# board1.net
KiCad netlist of a schematic drawn in EAGLE
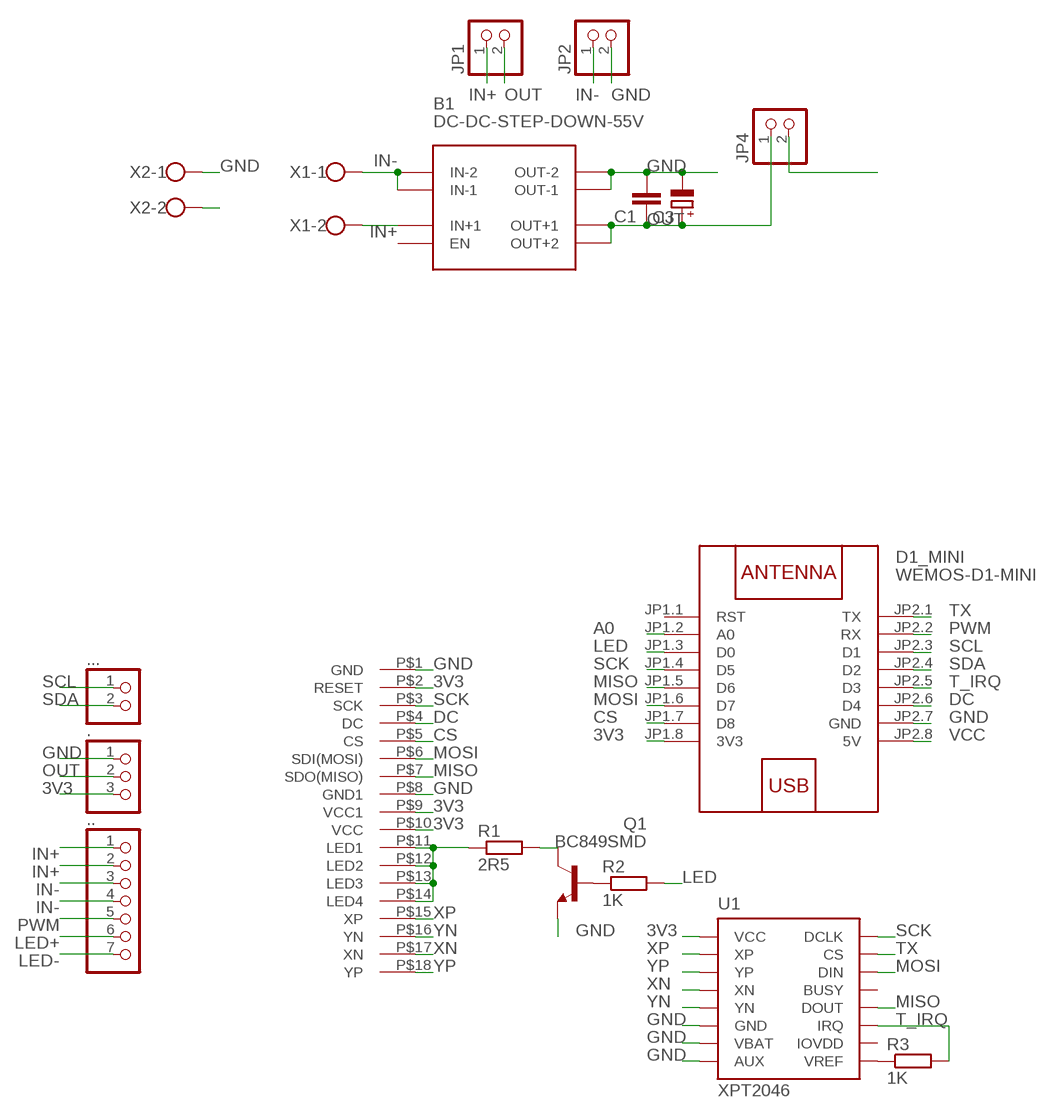
[diagram p0: schematic, sheet 1]

(export (version "E")
  (design (tool "Eeschema 10.0.6"))
  (components
    (comp (ref ".")
      (value "PINHD-1X3")
      (footprint "eagle-import:1X03")
      (libsource (lib "eagle-import") (part "PINHD-1X3"))
    )
    (comp (ref "..")
      (value "PINHD-1X7")
      (footprint "eagle-import:1X07")
      (libsource (lib "eagle-import") (part "PINHD-1X7"))
    )
    (comp (ref "...")
      (value "PINHD-1X2")
      (footprint "eagle-import:1X02")
      (libsource (lib "eagle-import") (part "PINHD-1X2"))
    )
    (comp (ref "B1")
      (value "DC-DC-STEP-DOWN-55V")
      (footprint "eagle-import:DC-DC-STEP-DOWN-55V")
      (libsource (lib "eagle-import") (part "DC-DC-STEP-DOWN-55V"))
    )
    (comp (ref "C1")
      (value "C-EUC0805")
      (footprint "eagle-import:C0805")
      (libsource (lib "eagle-import") (part "C-EUC0805"))
    )
    (comp (ref "C3")
      (value "CPOL-EUE2-5")
      (footprint "eagle-import:E2-5")
      (libsource (lib "eagle-import") (part "CPOL-EUE2-5"))
    )
    (comp (ref "D1_MINI")
      (value "WEMOS-D1-MINI")
      (footprint "eagle-import:WEMOS-D1-MINI")
      (libsource (lib "eagle-import") (part "WEMOS-D1-MINI"))
    )
    (comp (ref "JP1")
      (value "PINHD-1X2")
      (footprint "eagle-import:1X02")
      (libsource (lib "eagle-import") (part "PINHD-1X2"))
    )
    (comp (ref "JP2")
      (value "PINHD-1X2")
      (footprint "eagle-import:1X02")
      (libsource (lib "eagle-import") (part "PINHD-1X2"))
    )
    (comp (ref "JP4")
      (value "PINHD-1X2")
      (footprint "eagle-import:1X02")
      (libsource (lib "eagle-import") (part "PINHD-1X2"))
    )
    (comp (ref "Q1")
      (value "BC849SMD")
      (footprint "eagle-import:SOT23-BEC")
      (libsource (lib "eagle-import") (part "BC849SMD"))
    )
    (comp (ref "R1")
      (value "2R5")
      (footprint "eagle-import:R1210W")
      (libsource (lib "eagle-import") (part "R-EU_R1210W"))
    )
    (comp (ref "R2")
      (value "1K")
      (footprint "eagle-import:R1210W")
      (libsource (lib "eagle-import") (part "R-EU_R1210W"))
    )
    (comp (ref "R3")
      (value "1K")
      (footprint "eagle-import:R1210W")
      (libsource (lib "eagle-import") (part "R-EU_R1210W"))
    )
    (comp (ref "U$2")
      (value "2.4TTF")
      (footprint "eagle-import:TFT2.4")
      (libsource (lib "eagle-import") (part "2.4TTF"))
    )
    (comp (ref "U1")
      (value "XPT2046")
      (footprint "eagle-import:TSSOP16")
      (libsource (lib "eagle-import") (part "XPT2046"))
    )
    (comp (ref "X1")
      (value "W237-102")
      (footprint "eagle-import:W237-102")
      (fields (field (name "MPN") "237-102"))
      (libsource (lib "eagle-import") (part "W237-102"))
    )
    (comp (ref "X2")
      (value "W237-102")
      (footprint "eagle-import:W237-102")
      (fields (field (name "MPN") "237-102"))
      (libsource (lib "eagle-import") (part "W237-102"))
    )
  )
  (nets
    (net (code "1") (name "/3V3") (class "Default")
      (node (ref ".") (pin "3") (pinfunction "3_3") (pintype "passive"))
      (node (ref "D1_MINI") (pin "JP1.8") (pinfunction "3V3_JP1.8") (pintype "power_in"))
      (node (ref "U$2") (pin "P$10") (pinfunction "VCC_P$10") (pintype "bidirectional"))
      (node (ref "U$2") (pin "P$2") (pinfunction "RESET_P$2") (pintype "bidirectional"))
      (node (ref "U$2") (pin "P$9") (pinfunction "VCC1_P$9") (pintype "bidirectional"))
      (node (ref "U1") (pin "1") (pinfunction "VCC_1") (pintype "power_in"))
    )
    (net (code "2") (name "/A0") (class "Default")
      (node (ref "D1_MINI") (pin "JP1.2") (pinfunction "A0_JP1.2") (pintype "bidirectional"))
      (node (ref "X2") (pin "2") (pinfunction "KL_2") (pintype "passive"))
    )
    (net (code "3") (name "/CS") (class "Default")
      (node (ref "D1_MINI") (pin "JP1.7") (pinfunction "D8_JP1.7") (pintype "bidirectional"))
      (node (ref "U$2") (pin "P$5") (pinfunction "CS_P$5") (pintype "bidirectional"))
    )
    (net (code "4") (name "/DC") (class "Default")
      (node (ref "D1_MINI") (pin "JP2.6") (pinfunction "D4_JP2.6") (pintype "bidirectional"))
      (node (ref "U$2") (pin "P$4") (pinfunction "DC_P$4") (pintype "bidirectional"))
    )
    (net (code "5") (name "/GND") (class "Default")
      (node (ref ".") (pin "1") (pinfunction "1_1") (pintype "passive"))
      (node (ref "B1") (pin "VOUT-1") (pinfunction "OUT-1_VOUT-1") (pintype "bidirectional"))
      (node (ref "B1") (pin "VOUT-2") (pinfunction "OUT-2_VOUT-2") (pintype "bidirectional"))
      (node (ref "C1") (pin "2") (pinfunction "2_2") (pintype "passive"))
      (node (ref "C3") (pin "-") (pinfunction "-_-") (pintype "passive"))
      (node (ref "D1_MINI") (pin "JP2.7") (pinfunction "GND_JP2.7") (pintype "power_in"))
      (node (ref "JP2") (pin "2") (pinfunction "2_2") (pintype "passive"))
      (node (ref "Q1") (pin "E") (pinfunction "E_E") (pintype "passive"))
      (node (ref "U$2") (pin "P$1") (pinfunction "GND_P$1") (pintype "power_in"))
      (node (ref "U$2") (pin "P$8") (pinfunction "GND1_P$8") (pintype "power_in"))
      (node (ref "U1") (pin "6") (pinfunction "GND_6") (pintype "power_in"))
      (node (ref "U1") (pin "7") (pinfunction "VBAT_7") (pintype "bidirectional"))
      (node (ref "U1") (pin "8") (pinfunction "AUX_8") (pintype "bidirectional"))
      (node (ref "X2") (pin "1") (pinfunction "KL_1") (pintype "passive"))
    )
    (net (code "6") (name "/IN+") (class "Default")
      (node (ref "..") (pin "1") (pinfunction "1_1") (pintype "passive"))
      (node (ref "..") (pin "2") (pinfunction "2_2") (pintype "passive"))
      (node (ref "B1") (pin "VIN+") (pinfunction "IN+1_VIN+") (pintype "bidirectional"))
      (node (ref "JP1") (pin "1") (pinfunction "1_1") (pintype "passive"))
      (node (ref "X1") (pin "2") (pinfunction "KL_2") (pintype "passive"))
    )
    (net (code "7") (name "/IN-") (class "Default")
      (node (ref "..") (pin "3") (pinfunction "3_3") (pintype "passive"))
      (node (ref "..") (pin "4") (pinfunction "4_4") (pintype "passive"))
      (node (ref "B1") (pin "VIN-1") (pinfunction "IN-1_VIN-1") (pintype "bidirectional"))
      (node (ref "B1") (pin "VIN-2") (pinfunction "IN-2_VIN-2") (pintype "bidirectional"))
      (node (ref "JP2") (pin "1") (pinfunction "1_1") (pintype "passive"))
      (node (ref "X1") (pin "1") (pinfunction "KL_1") (pintype "passive"))
    )
    (net (code "8") (name "/LED") (class "Default")
      (node (ref "D1_MINI") (pin "JP1.3") (pinfunction "D0_JP1.3") (pintype "bidirectional"))
      (node (ref "R2") (pin "2") (pinfunction "2_2") (pintype "passive"))
    )
    (net (code "9") (name "/LED+") (class "Default")
      (node (ref "..") (pin "6") (pinfunction "6_6") (pintype "passive"))
    )
    (net (code "10") (name "/LED-") (class "Default")
      (node (ref "..") (pin "7") (pinfunction "7_7") (pintype "passive"))
    )
    (net (code "11") (name "/MISO") (class "Default")
      (node (ref "D1_MINI") (pin "JP1.5") (pinfunction "D6_JP1.5") (pintype "bidirectional"))
      (node (ref "U$2") (pin "P$7") (pinfunction "SDO(MISO)_P$7") (pintype "bidirectional"))
      (node (ref "U1") (pin "12") (pinfunction "DOUT_12") (pintype "output"))
    )
    (net (code "12") (name "/MOSI") (class "Default")
      (node (ref "D1_MINI") (pin "JP1.6") (pinfunction "D7_JP1.6") (pintype "bidirectional"))
      (node (ref "U$2") (pin "P$6") (pinfunction "SDI(MOSI)_P$6") (pintype "bidirectional"))
      (node (ref "U1") (pin "14") (pinfunction "DIN_14") (pintype "input"))
    )
    (net (code "13") (name "/OUT") (class "Default")
      (node (ref ".") (pin "2") (pinfunction "2_2") (pintype "passive"))
      (node (ref "B1") (pin "VOUT+1") (pinfunction "OUT+1_VOUT+1") (pintype "bidirectional"))
      (node (ref "B1") (pin "VOUT+2") (pinfunction "OUT+2_VOUT+2") (pintype "bidirectional"))
      (node (ref "C1") (pin "1") (pinfunction "1_1") (pintype "passive"))
      (node (ref "C3") (pin "+") (pinfunction "+_+") (pintype "passive"))
      (node (ref "JP1") (pin "2") (pinfunction "2_2") (pintype "passive"))
      (node (ref "JP4") (pin "1") (pinfunction "1_1") (pintype "passive"))
    )
    (net (code "14") (name "/PWM") (class "Default")
      (node (ref "..") (pin "5") (pinfunction "5_5") (pintype "passive"))
      (node (ref "D1_MINI") (pin "JP2.2") (pinfunction "RX_JP2.2") (pintype "bidirectional"))
    )
    (net (code "15") (name "/SCK") (class "Default")
      (node (ref "D1_MINI") (pin "JP1.4") (pinfunction "D5_JP1.4") (pintype "bidirectional"))
      (node (ref "U$2") (pin "P$3") (pinfunction "SCK_P$3") (pintype "bidirectional"))
      (node (ref "U1") (pin "16") (pinfunction "DCLK_16") (pintype "input"))
    )
    (net (code "16") (name "/SCL") (class "Default")
      (node (ref "...") (pin "1") (pinfunction "1_1") (pintype "passive"))
      (node (ref "D1_MINI") (pin "JP2.3") (pinfunction "D1_JP2.3") (pintype "bidirectional"))
    )
    (net (code "17") (name "/SDA") (class "Default")
      (node (ref "...") (pin "2") (pinfunction "2_2") (pintype "passive"))
      (node (ref "D1_MINI") (pin "JP2.4") (pinfunction "D2_JP2.4") (pintype "bidirectional"))
    )
    (net (code "18") (name "/TX") (class "Default")
      (node (ref "D1_MINI") (pin "JP2.1") (pinfunction "TX_JP2.1") (pintype "bidirectional"))
      (node (ref "U1") (pin "15") (pinfunction "CS_15") (pintype "bidirectional"))
    )
    (net (code "19") (name "/T_IRQ") (class "Default")
      (node (ref "D1_MINI") (pin "JP2.5") (pinfunction "D3_JP2.5") (pintype "bidirectional"))
      (node (ref "R3") (pin "2") (pinfunction "2_2") (pintype "passive"))
      (node (ref "U1") (pin "11") (pinfunction "IRQ_11") (pintype "bidirectional"))
    )
    (net (code "20") (name "/VCC") (class "Default")
      (node (ref "D1_MINI") (pin "JP2.8") (pinfunction "5V_JP2.8") (pintype "power_in"))
      (node (ref "JP4") (pin "2") (pinfunction "2_2") (pintype "passive"))
    )
    (net (code "21") (name "/XN") (class "Default")
      (node (ref "U$2") (pin "P$17") (pinfunction "XN_P$17") (pintype "bidirectional"))
      (node (ref "U1") (pin "4") (pinfunction "XN_4") (pintype "bidirectional"))
    )
    (net (code "22") (name "/XP") (class "Default")
      (node (ref "U$2") (pin "P$15") (pinfunction "XP_P$15") (pintype "bidirectional"))
      (node (ref "U1") (pin "2") (pinfunction "XP_2") (pintype "bidirectional"))
    )
    (net (code "23") (name "/YN") (class "Default")
      (node (ref "U$2") (pin "P$16") (pinfunction "YN_P$16") (pintype "bidirectional"))
      (node (ref "U1") (pin "5") (pinfunction "YN_5") (pintype "bidirectional"))
    )
    (net (code "24") (name "/YP") (class "Default")
      (node (ref "U$2") (pin "P$18") (pinfunction "YP_P$18") (pintype "bidirectional"))
      (node (ref "U1") (pin "3") (pinfunction "YP_3") (pintype "bidirectional"))
    )
    (net (code "25") (name "Net-(Q1-PadB)") (class "Default")
      (node (ref "Q1") (pin "B") (pinfunction "B_B") (pintype "passive"))
      (node (ref "R2") (pin "1") (pinfunction "1_1") (pintype "passive"))
    )
    (net (code "26") (name "Net-(Q1-PadC)") (class "Default")
      (node (ref "Q1") (pin "C") (pinfunction "C_C") (pintype "passive"))
      (node (ref "R1") (pin "2") (pinfunction "2_2") (pintype "passive"))
    )
    (net (code "27") (name "Net-(U$2-LED1)") (class "Default")
      (node (ref "R1") (pin "1") (pinfunction "1_1") (pintype "passive"))
      (node (ref "U$2") (pin "P$11") (pinfunction "LED1_P$11") (pintype "bidirectional"))
      (node (ref "U$2") (pin "P$12") (pinfunction "LED2_P$12") (pintype "bidirectional"))
      (node (ref "U$2") (pin "P$13") (pinfunction "LED3_P$13") (pintype "bidirectional"))
      (node (ref "U$2") (pin "P$14") (pinfunction "LED4_P$14") (pintype "bidirectional"))
    )
    (net (code "28") (name "Net-(U1-VREF)") (class "Default")
      (node (ref "R3") (pin "1") (pinfunction "1_1") (pintype "passive"))
      (node (ref "U1") (pin "9") (pinfunction "VREF_9") (pintype "bidirectional"))
    )
    (net (code "29") (name "unconnected-(B1-PadEN)") (class "Default")
      (node (ref "B1") (pin "EN") (pinfunction "EN_EN") (pintype "bidirectional"))
    )
    (net (code "30") (name "unconnected-(D1_MINI-RST-PadJP1.1)") (class "Default")
      (node (ref "D1_MINI") (pin "JP1.1") (pinfunction "RST_JP1.1") (pintype "bidirectional"))
    )
    (net (code "31") (name "unconnected-(U1-BUSY-Pad13)") (class "Default")
      (node (ref "U1") (pin "13") (pinfunction "BUSY_13") (pintype "input"))
    )
    (net (code "32") (name "unconnected-(U1-IOVDD-Pad10)") (class "Default")
      (node (ref "U1") (pin "10") (pinfunction "IOVDD_10") (pintype "bidirectional"))
    )
  )
)
